# A540R260_ARM2.net
KiCad netlist of a schematic drawn in Altium Designer
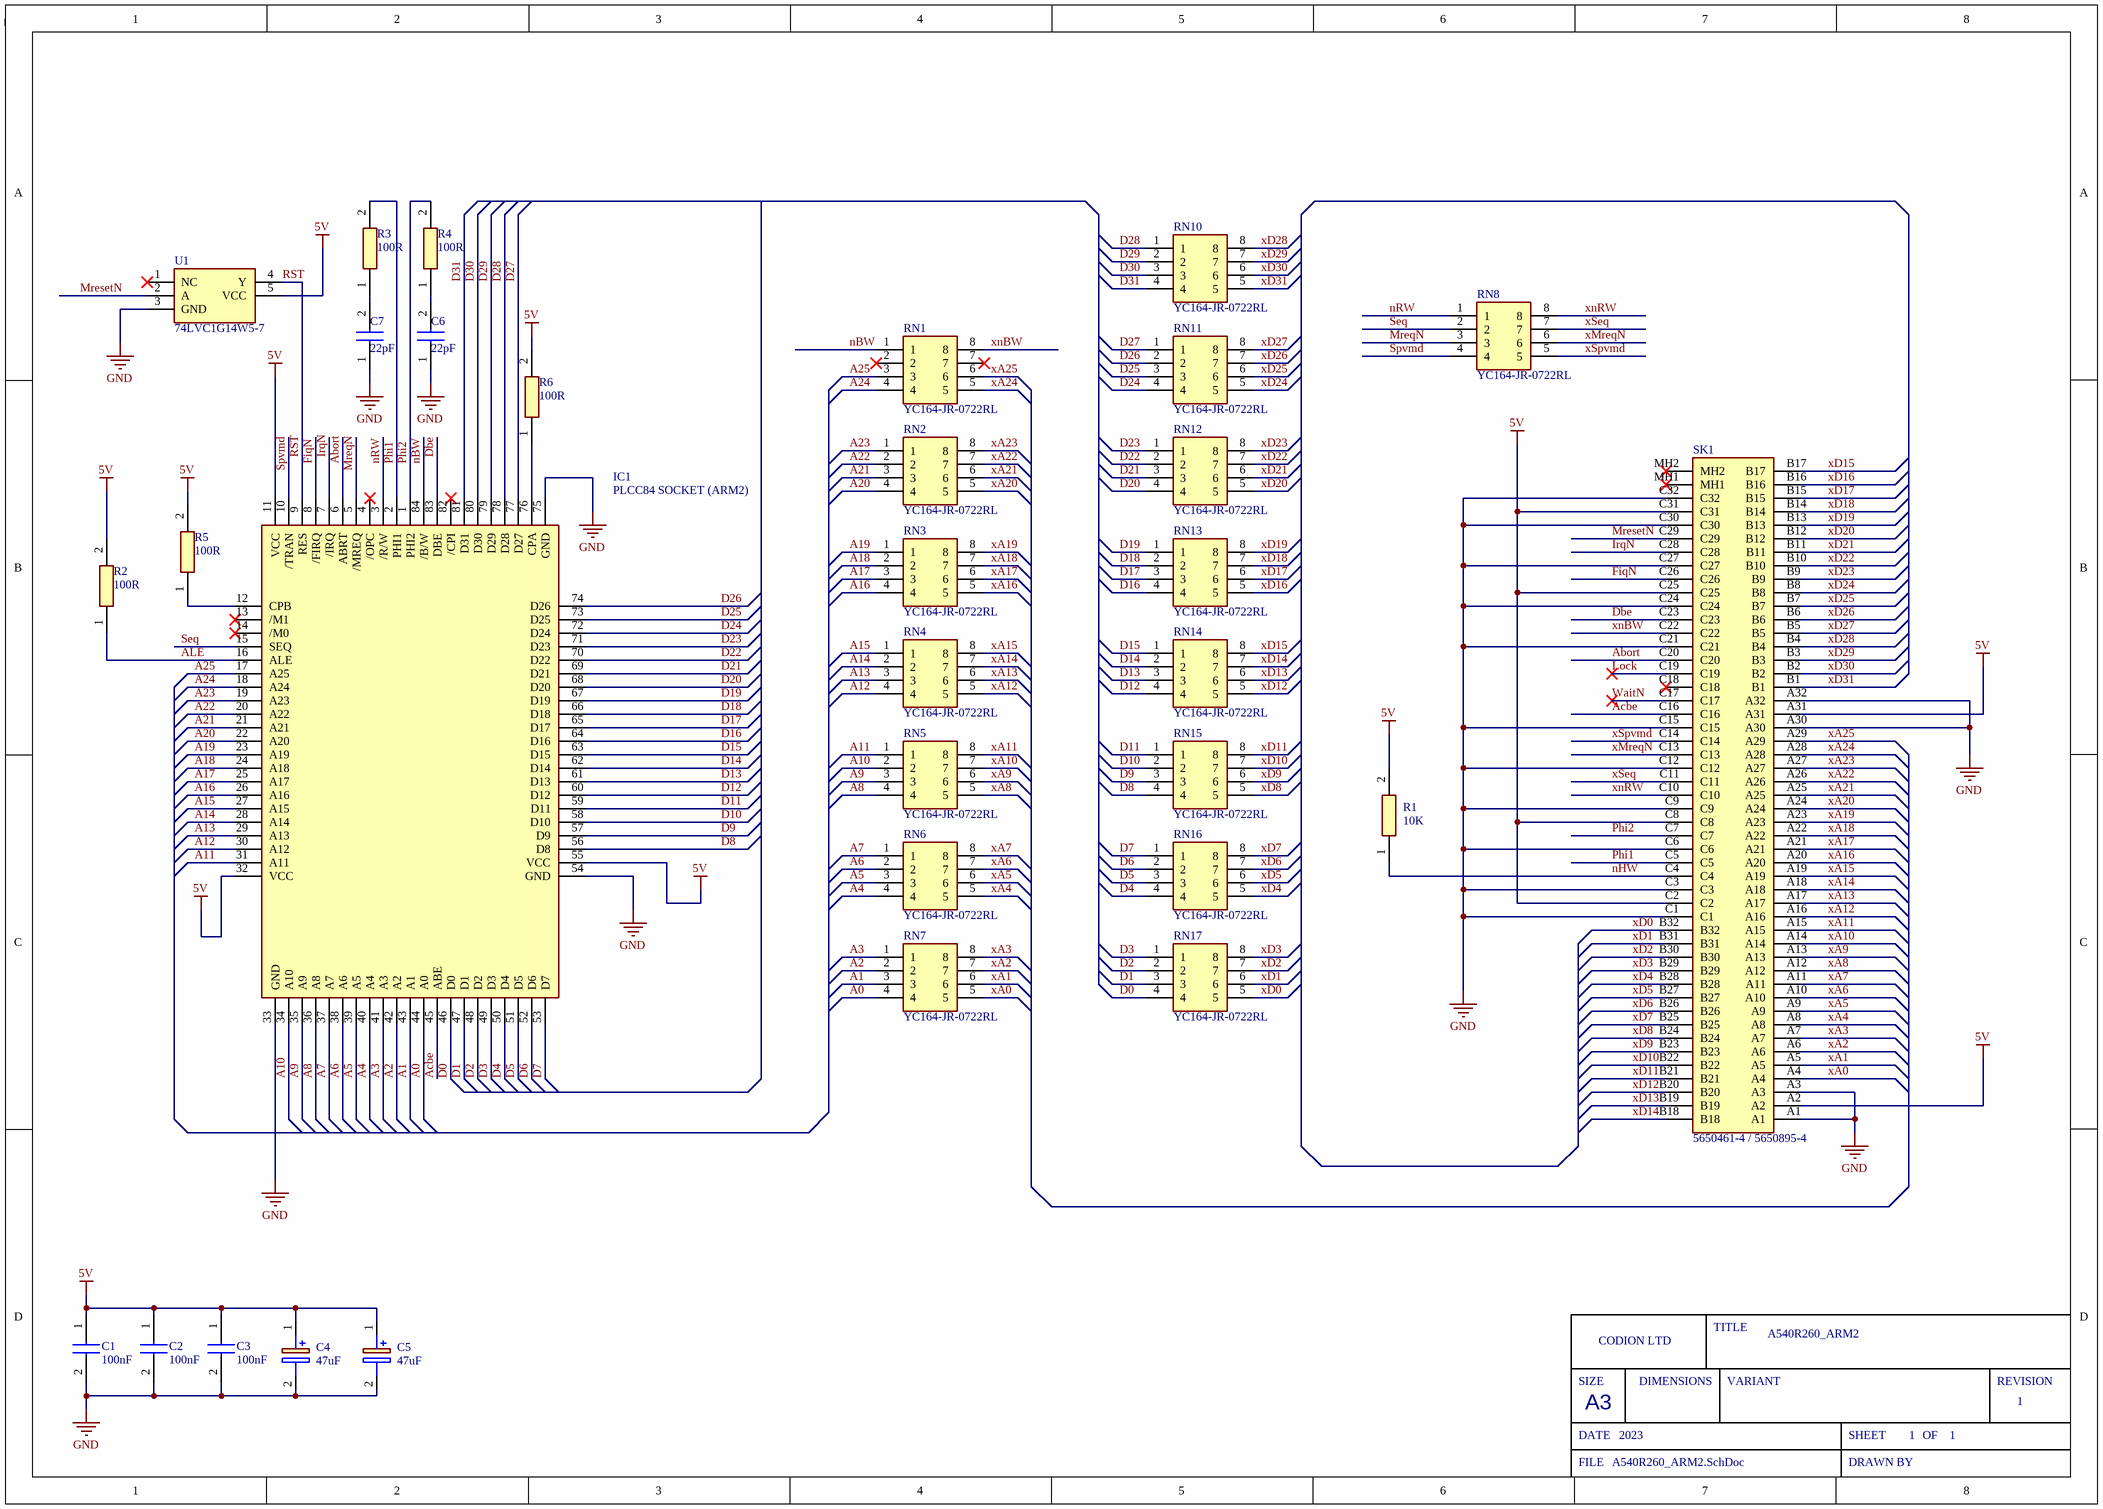
[diagram p0: A540R260_ARM2.SchDoc]

(export (version "E")
  (design (tool "Eeschema 10.0.6"))
  (components
    (comp (ref "C1")
      (value "100nF")
      (footprint "SamacSys:CAPC2012X145N")
      (description "Capacitor")
      (fields
        (field (name "MANUFACTURER_PART_NUMBER") "C2012X7R1H104K125AM")
        (field (name "MOUSER PART NUMBER") "810-C2012X7R1H104KT5")
      )
      (libsource (lib "*") (part "C2012X7R1H104K125AM"))
    )
    (comp (ref "C2")
      (value "100nF")
      (footprint "SamacSys:CAPC2012X145N")
      (description "Capacitor")
      (fields
        (field (name "MANUFACTURER_PART_NUMBER") "C2012X7R1H104K125AM")
        (field (name "MOUSER PART NUMBER") "810-C2012X7R1H104KT5")
      )
      (libsource (lib "*") (part "C2012X7R1H104K125AM"))
    )
    (comp (ref "C3")
      (value "100nF")
      (footprint "SamacSys:CAPC2012X145N")
      (description "Capacitor")
      (fields
        (field (name "MANUFACTURER_PART_NUMBER") "C2012X7R1H104K125AM")
        (field (name "MOUSER PART NUMBER") "810-C2012X7R1H104KT5")
      )
      (libsource (lib "*") (part "C2012X7R1H104K125AM"))
    )
    (comp (ref "C4")
      (value "47uF")
      (footprint "SamacSys:EEE1AA101SP")
      (description "Capacitor Polarised")
      (fields (field (name "MANUFACTURER_PART_NUMBER") "EEE1VA470WP"))
      (libsource (lib "*") (part "EEE1VA470WP"))
    )
    (comp (ref "C5")
      (value "47uF")
      (footprint "SamacSys:EEE1AA101SP")
      (description "Capacitor Polarised")
      (fields (field (name "MANUFACTURER_PART_NUMBER") "EEE1VA470WP"))
      (libsource (lib "*") (part "EEE1VA470WP"))
    )
    (comp (ref "C6")
      (value "22pF")
      (footprint "SamacSys:C0805")
      (description "Capacitor")
      (fields
        (field (name "MANUFACTURER_PART_NUMBER") "C0805C220J5GACTU")
        (field (name "MOUSER PART NUMBER") "80-C0805C220J5G")
      )
      (libsource (lib "*") (part "C0805C220J5GACTU"))
    )
    (comp (ref "C7")
      (value "22pF")
      (footprint "SamacSys:C0805")
      (description "Capacitor")
      (fields
        (field (name "MANUFACTURER_PART_NUMBER") "C0805C220J5GACTU")
        (field (name "MOUSER PART NUMBER") "80-C0805C220J5G")
      )
      (libsource (lib "*") (part "C0805C220J5GACTU"))
    )
    (comp (ref "IC1")
      (value "PLCC84 SOCKET (ARM2)")
      (footprint "PLCC84_PLUG")
      (description "PLCC84 Plug")
      (fields (field (name "MANUFACTURER_PART_NUMBER") "W9328"))
      (libsource (lib "ARM2toARM3Adapter") (part "PLCC84_PLUG_ARM2"))
    )
    (comp (ref "R1")
      (value "10K")
      (footprint "SamacSys:RESC2012X60N")
      (description "Resistor")
      (fields
        (field (name "MANUFACTURER_PART_NUMBER") "RC0805JR-0710KL")
        (field (name "MOUSER PART NUMBER") "603-RC0805JR-0710KL")
      )
      (libsource (lib "*") (part "RC0805JR-0710KL"))
    )
    (comp (ref "R2")
      (value "100R")
      (footprint "SamacSys:RESC2012X60N")
      (description "Resistor")
      (fields
        (field (name "MANUFACTURER_PART_NUMBER") "RC0805FR-07100RL")
        (field (name "MOUSER PART NUMBER") "603-RC0805FR-07100RL")
      )
      (libsource (lib "*") (part "RC0805FR-07100RL"))
    )
    (comp (ref "R3")
      (value "100R")
      (footprint "SamacSys:RESC2012X60N")
      (description "Resistor")
      (fields
        (field (name "MANUFACTURER_PART_NUMBER") "RC0805FR-07100RL")
        (field (name "MOUSER PART NUMBER") "603-RC0805FR-07100RL")
      )
      (libsource (lib "*") (part "RC0805FR-07100RL"))
    )
    (comp (ref "R4")
      (value "100R")
      (footprint "SamacSys:RESC2012X60N")
      (description "Resistor")
      (fields
        (field (name "MANUFACTURER_PART_NUMBER") "RC0805FR-07100RL")
        (field (name "MOUSER PART NUMBER") "603-RC0805FR-07100RL")
      )
      (libsource (lib "*") (part "RC0805FR-07100RL"))
    )
    (comp (ref "R5")
      (value "100R")
      (footprint "SamacSys:RESC2012X60N")
      (description "Resistor")
      (fields
        (field (name "MANUFACTURER_PART_NUMBER") "RC0805FR-07100RL")
        (field (name "MOUSER PART NUMBER") "603-RC0805FR-07100RL")
      )
      (libsource (lib "*") (part "RC0805FR-07100RL"))
    )
    (comp (ref "R6")
      (value "100R")
      (footprint "SamacSys:RESC2012X60N")
      (description "Resistor")
      (fields
        (field (name "MANUFACTURER_PART_NUMBER") "RC0805FR-07100RL")
        (field (name "MOUSER PART NUMBER") "603-RC0805FR-07100RL")
      )
      (libsource (lib "*") (part "RC0805FR-07100RL"))
    )
    (comp (ref "RN1")
      (value "YC164-JR-0722RL")
      (footprint "SamacSys:YC164JR072K2L")
      (description "Resistor Network")
      (fields (field (name "MOUSER PART NUMBER") "603-YC164-JR-0722RL"))
      (libsource (lib "*") (part "YC164-JR-0722RL"))
    )
    (comp (ref "RN2")
      (value "YC164-JR-0722RL")
      (footprint "SamacSys:YC164JR072K2L")
      (description "Resistor Network")
      (fields (field (name "MOUSER PART NUMBER") "603-YC164-JR-0722RL"))
      (libsource (lib "*") (part "YC164-JR-0722RL"))
    )
    (comp (ref "RN3")
      (value "YC164-JR-0722RL")
      (footprint "SamacSys:YC164JR072K2L")
      (description "Resistor Network")
      (fields (field (name "MOUSER PART NUMBER") "603-YC164-JR-0722RL"))
      (libsource (lib "*") (part "YC164-JR-0722RL"))
    )
    (comp (ref "RN4")
      (value "YC164-JR-0722RL")
      (footprint "SamacSys:YC164JR072K2L")
      (description "Resistor Network")
      (fields (field (name "MOUSER PART NUMBER") "603-YC164-JR-0722RL"))
      (libsource (lib "*") (part "YC164-JR-0722RL"))
    )
    (comp (ref "RN5")
      (value "YC164-JR-0722RL")
      (footprint "SamacSys:YC164JR072K2L")
      (description "Resistor Network")
      (fields (field (name "MOUSER PART NUMBER") "603-YC164-JR-0722RL"))
      (libsource (lib "*") (part "YC164-JR-0722RL"))
    )
    (comp (ref "RN6")
      (value "YC164-JR-0722RL")
      (footprint "SamacSys:YC164JR072K2L")
      (description "Resistor Network")
      (fields (field (name "MOUSER PART NUMBER") "603-YC164-JR-0722RL"))
      (libsource (lib "*") (part "YC164-JR-0722RL"))
    )
    (comp (ref "RN7")
      (value "YC164-JR-0722RL")
      (footprint "SamacSys:YC164JR072K2L")
      (description "Resistor Network")
      (fields (field (name "MOUSER PART NUMBER") "603-YC164-JR-0722RL"))
      (libsource (lib "*") (part "YC164-JR-0722RL"))
    )
    (comp (ref "RN8")
      (value "YC164-JR-0722RL")
      (footprint "SamacSys:YC164JR072K2L")
      (description "Resistor Network")
      (fields (field (name "MOUSER PART NUMBER") "603-YC164-JR-0722RL"))
      (libsource (lib "*") (part "YC164-JR-0722RL"))
    )
    (comp (ref "RN10")
      (value "YC164-JR-0722RL")
      (footprint "SamacSys:YC164JR072K2L")
      (description "Resistor Network")
      (fields (field (name "MOUSER PART NUMBER") "603-YC164-JR-0722RL"))
      (libsource (lib "*") (part "YC164-JR-0722RL"))
    )
    (comp (ref "RN11")
      (value "YC164-JR-0722RL")
      (footprint "SamacSys:YC164JR072K2L")
      (description "Resistor Network")
      (fields (field (name "MOUSER PART NUMBER") "603-YC164-JR-0722RL"))
      (libsource (lib "*") (part "YC164-JR-0722RL"))
    )
    (comp (ref "RN12")
      (value "YC164-JR-0722RL")
      (footprint "SamacSys:YC164JR072K2L")
      (description "Resistor Network")
      (fields (field (name "MOUSER PART NUMBER") "603-YC164-JR-0722RL"))
      (libsource (lib "*") (part "YC164-JR-0722RL"))
    )
    (comp (ref "RN13")
      (value "YC164-JR-0722RL")
      (footprint "SamacSys:YC164JR072K2L")
      (description "Resistor Network")
      (fields (field (name "MOUSER PART NUMBER") "603-YC164-JR-0722RL"))
      (libsource (lib "*") (part "YC164-JR-0722RL"))
    )
    (comp (ref "RN14")
      (value "YC164-JR-0722RL")
      (footprint "SamacSys:YC164JR072K2L")
      (description "Resistor Network")
      (fields (field (name "MOUSER PART NUMBER") "603-YC164-JR-0722RL"))
      (libsource (lib "*") (part "YC164-JR-0722RL"))
    )
    (comp (ref "RN15")
      (value "YC164-JR-0722RL")
      (footprint "SamacSys:YC164JR072K2L")
      (description "Resistor Network")
      (fields (field (name "MOUSER PART NUMBER") "603-YC164-JR-0722RL"))
      (libsource (lib "*") (part "YC164-JR-0722RL"))
    )
    (comp (ref "RN16")
      (value "YC164-JR-0722RL")
      (footprint "SamacSys:YC164JR072K2L")
      (description "Resistor Network")
      (fields (field (name "MOUSER PART NUMBER") "603-YC164-JR-0722RL"))
      (libsource (lib "*") (part "YC164-JR-0722RL"))
    )
    (comp (ref "RN17")
      (value "YC164-JR-0722RL")
      (footprint "SamacSys:YC164JR072K2L")
      (description "Resistor Network")
      (fields (field (name "MOUSER PART NUMBER") "603-YC164-JR-0722RL"))
      (libsource (lib "*") (part "YC164-JR-0722RL"))
    )
    (comp (ref "SK1")
      (value "5650461-4 / 5650895-4")
      (footprint "SamacSys:56504614")
      (description "Connector")
      (fields
        (field (name "MANUFACTURER_PART_NUMBER") "5650461-4")
        (field (name "MOUSER PART NUMBER") "571-5650461-4")
      )
      (libsource (lib "*") (part "5650461-4"))
    )
    (comp (ref "U1")
      (value "74LVC1G14W5-7")
      (footprint "SamacSys:SOT95P285X140-5N")
      (description "Undefined or Miscellaneous")
      (fields (field (name "MOUSER PART NUMBER") "621-74LVC1G14W5-7"))
      (libsource (lib "*") (part "74LVC1G14W5-7"))
    )
  )
  (nets
    (net (code "1") (name "/A0") (class "Default")
      (node (ref "IC1") (pin "44") (pinfunction "A0_44") (pintype "passive"))
      (node (ref "RN7") (pin "4") (pinfunction "4_4") (pintype "passive"))
    )
    (net (code "2") (name "/A1") (class "Default")
      (node (ref "IC1") (pin "43") (pinfunction "A1_43") (pintype "passive"))
      (node (ref "RN7") (pin "3") (pinfunction "3_3") (pintype "passive"))
    )
    (net (code "3") (name "/A2") (class "Default")
      (node (ref "IC1") (pin "42") (pinfunction "A2_42") (pintype "passive"))
      (node (ref "RN7") (pin "2") (pinfunction "2_2") (pintype "passive"))
    )
    (net (code "4") (name "/A3") (class "Default")
      (node (ref "IC1") (pin "41") (pinfunction "A3_41") (pintype "passive"))
      (node (ref "RN7") (pin "1") (pinfunction "1_1") (pintype "passive"))
    )
    (net (code "5") (name "/A4") (class "Default")
      (node (ref "IC1") (pin "40") (pinfunction "A4_40") (pintype "passive"))
      (node (ref "RN6") (pin "4") (pinfunction "4_4") (pintype "passive"))
    )
    (net (code "6") (name "/A5") (class "Default")
      (node (ref "IC1") (pin "39") (pinfunction "A5_39") (pintype "passive"))
      (node (ref "RN6") (pin "3") (pinfunction "3_3") (pintype "passive"))
    )
    (net (code "7") (name "/A6") (class "Default")
      (node (ref "IC1") (pin "38") (pinfunction "A6_38") (pintype "passive"))
      (node (ref "RN6") (pin "2") (pinfunction "2_2") (pintype "passive"))
    )
    (net (code "8") (name "/A7") (class "Default")
      (node (ref "IC1") (pin "37") (pinfunction "A7_37") (pintype "passive"))
      (node (ref "RN6") (pin "1") (pinfunction "1_1") (pintype "passive"))
    )
    (net (code "9") (name "/A8") (class "Default")
      (node (ref "IC1") (pin "36") (pinfunction "A8_36") (pintype "passive"))
      (node (ref "RN5") (pin "4") (pinfunction "4_4") (pintype "passive"))
    )
    (net (code "10") (name "/A9") (class "Default")
      (node (ref "IC1") (pin "35") (pinfunction "A9_35") (pintype "passive"))
      (node (ref "RN5") (pin "3") (pinfunction "3_3") (pintype "passive"))
    )
    (net (code "11") (name "/A10") (class "Default")
      (node (ref "IC1") (pin "34") (pinfunction "A10_34") (pintype "passive"))
      (node (ref "RN5") (pin "2") (pinfunction "2_2") (pintype "passive"))
    )
    (net (code "12") (name "/A11") (class "Default")
      (node (ref "IC1") (pin "31") (pinfunction "A11_31") (pintype "passive"))
      (node (ref "RN5") (pin "1") (pinfunction "1_1") (pintype "passive"))
    )
    (net (code "13") (name "/A12") (class "Default")
      (node (ref "IC1") (pin "30") (pinfunction "A12_30") (pintype "passive"))
      (node (ref "RN4") (pin "4") (pinfunction "4_4") (pintype "passive"))
    )
    (net (code "14") (name "/A13") (class "Default")
      (node (ref "IC1") (pin "29") (pinfunction "A13_29") (pintype "passive"))
      (node (ref "RN4") (pin "3") (pinfunction "3_3") (pintype "passive"))
    )
    (net (code "15") (name "/A14") (class "Default")
      (node (ref "IC1") (pin "28") (pinfunction "A14_28") (pintype "passive"))
      (node (ref "RN4") (pin "2") (pinfunction "2_2") (pintype "passive"))
    )
    (net (code "16") (name "/A15") (class "Default")
      (node (ref "IC1") (pin "27") (pinfunction "A15_27") (pintype "passive"))
      (node (ref "RN4") (pin "1") (pinfunction "1_1") (pintype "passive"))
    )
    (net (code "17") (name "/A16") (class "Default")
      (node (ref "IC1") (pin "26") (pinfunction "A16_26") (pintype "passive"))
      (node (ref "RN3") (pin "4") (pinfunction "4_4") (pintype "passive"))
    )
    (net (code "18") (name "/A17") (class "Default")
      (node (ref "IC1") (pin "25") (pinfunction "A17_25") (pintype "passive"))
      (node (ref "RN3") (pin "3") (pinfunction "3_3") (pintype "passive"))
    )
    (net (code "19") (name "/A18") (class "Default")
      (node (ref "IC1") (pin "24") (pinfunction "A18_24") (pintype "passive"))
      (node (ref "RN3") (pin "2") (pinfunction "2_2") (pintype "passive"))
    )
    (net (code "20") (name "/A19") (class "Default")
      (node (ref "IC1") (pin "23") (pinfunction "A19_23") (pintype "passive"))
      (node (ref "RN3") (pin "1") (pinfunction "1_1") (pintype "passive"))
    )
    (net (code "21") (name "/A20") (class "Default")
      (node (ref "IC1") (pin "22") (pinfunction "A20_22") (pintype "passive"))
      (node (ref "RN2") (pin "4") (pinfunction "4_4") (pintype "passive"))
    )
    (net (code "22") (name "/A21") (class "Default")
      (node (ref "IC1") (pin "21") (pinfunction "A21_21") (pintype "passive"))
      (node (ref "RN2") (pin "3") (pinfunction "3_3") (pintype "passive"))
    )
    (net (code "23") (name "/A22") (class "Default")
      (node (ref "IC1") (pin "20") (pinfunction "A22_20") (pintype "passive"))
      (node (ref "RN2") (pin "2") (pinfunction "2_2") (pintype "passive"))
    )
    (net (code "24") (name "/A23") (class "Default")
      (node (ref "IC1") (pin "19") (pinfunction "A23_19") (pintype "passive"))
      (node (ref "RN2") (pin "1") (pinfunction "1_1") (pintype "passive"))
    )
    (net (code "25") (name "/A24") (class "Default")
      (node (ref "IC1") (pin "18") (pinfunction "A24_18") (pintype "passive"))
      (node (ref "RN1") (pin "4") (pinfunction "4_4") (pintype "passive"))
    )
    (net (code "26") (name "/A25") (class "Default")
      (node (ref "IC1") (pin "17") (pinfunction "A25_17") (pintype "passive"))
      (node (ref "RN1") (pin "3") (pinfunction "3_3") (pintype "passive"))
    )
    (net (code "27") (name "/ALE") (class "Default")
      (node (ref "IC1") (pin "16") (pinfunction "ALE_16") (pintype "passive"))
      (node (ref "R2") (pin "1") (pinfunction "1_1") (pintype "passive"))
    )
    (net (code "28") (name "/Abort") (class "Default")
      (node (ref "IC1") (pin "6") (pinfunction "ABRT_6") (pintype "passive"))
      (node (ref "SK1") (pin "C20") (pinfunction "C20_C20") (pintype "passive"))
    )
    (net (code "29") (name "/Acbe") (class "Default")
      (node (ref "IC1") (pin "45") (pinfunction "ABE_45") (pintype "passive"))
      (node (ref "SK1") (pin "C16") (pinfunction "C16_C16") (pintype "passive"))
    )
    (net (code "30") (name "/D0") (class "Default")
      (node (ref "IC1") (pin "46") (pinfunction "D0_46") (pintype "passive"))
      (node (ref "RN17") (pin "4") (pinfunction "4_4") (pintype "passive"))
    )
    (net (code "31") (name "/D1") (class "Default")
      (node (ref "IC1") (pin "47") (pinfunction "D1_47") (pintype "passive"))
      (node (ref "RN17") (pin "3") (pinfunction "3_3") (pintype "passive"))
    )
    (net (code "32") (name "/D2") (class "Default")
      (node (ref "IC1") (pin "48") (pinfunction "D2_48") (pintype "passive"))
      (node (ref "RN17") (pin "2") (pinfunction "2_2") (pintype "passive"))
    )
    (net (code "33") (name "/D3") (class "Default")
      (node (ref "IC1") (pin "49") (pinfunction "D3_49") (pintype "passive"))
      (node (ref "RN17") (pin "1") (pinfunction "1_1") (pintype "passive"))
    )
    (net (code "34") (name "/D4") (class "Default")
      (node (ref "IC1") (pin "50") (pinfunction "D4_50") (pintype "passive"))
      (node (ref "RN16") (pin "4") (pinfunction "4_4") (pintype "passive"))
    )
    (net (code "35") (name "/D5") (class "Default")
      (node (ref "IC1") (pin "51") (pinfunction "D5_51") (pintype "passive"))
      (node (ref "RN16") (pin "3") (pinfunction "3_3") (pintype "passive"))
    )
    (net (code "36") (name "/D6") (class "Default")
      (node (ref "IC1") (pin "52") (pinfunction "D6_52") (pintype "passive"))
      (node (ref "RN16") (pin "2") (pinfunction "2_2") (pintype "passive"))
    )
    (net (code "37") (name "/D7") (class "Default")
      (node (ref "IC1") (pin "53") (pinfunction "D7_53") (pintype "passive"))
      (node (ref "RN16") (pin "1") (pinfunction "1_1") (pintype "passive"))
    )
    (net (code "38") (name "/D8") (class "Default")
      (node (ref "IC1") (pin "56") (pinfunction "D8_56") (pintype "passive"))
      (node (ref "RN15") (pin "4") (pinfunction "4_4") (pintype "passive"))
    )
    (net (code "39") (name "/D9") (class "Default")
      (node (ref "IC1") (pin "57") (pinfunction "D9_57") (pintype "passive"))
      (node (ref "RN15") (pin "3") (pinfunction "3_3") (pintype "passive"))
    )
    (net (code "40") (name "/D10") (class "Default")
      (node (ref "IC1") (pin "58") (pinfunction "D10_58") (pintype "passive"))
      (node (ref "RN15") (pin "2") (pinfunction "2_2") (pintype "passive"))
    )
    (net (code "41") (name "/D11") (class "Default")
      (node (ref "IC1") (pin "59") (pinfunction "D11_59") (pintype "passive"))
      (node (ref "RN15") (pin "1") (pinfunction "1_1") (pintype "passive"))
    )
    (net (code "42") (name "/D12") (class "Default")
      (node (ref "IC1") (pin "60") (pinfunction "D12_60") (pintype "passive"))
      (node (ref "RN14") (pin "4") (pinfunction "4_4") (pintype "passive"))
    )
    (net (code "43") (name "/D13") (class "Default")
      (node (ref "IC1") (pin "61") (pinfunction "D13_61") (pintype "passive"))
      (node (ref "RN14") (pin "3") (pinfunction "3_3") (pintype "passive"))
    )
    (net (code "44") (name "/D14") (class "Default")
      (node (ref "IC1") (pin "62") (pinfunction "D14_62") (pintype "passive"))
      (node (ref "RN14") (pin "2") (pinfunction "2_2") (pintype "passive"))
    )
    (net (code "45") (name "/D15") (class "Default")
      (node (ref "IC1") (pin "63") (pinfunction "D15_63") (pintype "passive"))
      (node (ref "RN14") (pin "1") (pinfunction "1_1") (pintype "passive"))
    )
    (net (code "46") (name "/D16") (class "Default")
      (node (ref "IC1") (pin "64") (pinfunction "D16_64") (pintype "passive"))
      (node (ref "RN13") (pin "4") (pinfunction "4_4") (pintype "passive"))
    )
    (net (code "47") (name "/D17") (class "Default")
      (node (ref "IC1") (pin "65") (pinfunction "D17_65") (pintype "passive"))
      (node (ref "RN13") (pin "3") (pinfunction "3_3") (pintype "passive"))
    )
    (net (code "48") (name "/D18") (class "Default")
      (node (ref "IC1") (pin "66") (pinfunction "D18_66") (pintype "passive"))
      (node (ref "RN13") (pin "2") (pinfunction "2_2") (pintype "passive"))
    )
    (net (code "49") (name "/D19") (class "Default")
      (node (ref "IC1") (pin "67") (pinfunction "D19_67") (pintype "passive"))
      (node (ref "RN13") (pin "1") (pinfunction "1_1") (pintype "passive"))
    )
    (net (code "50") (name "/D20") (class "Default")
      (node (ref "IC1") (pin "68") (pinfunction "D20_68") (pintype "passive"))
      (node (ref "RN12") (pin "4") (pinfunction "4_4") (pintype "passive"))
    )
    (net (code "51") (name "/D21") (class "Default")
      (node (ref "IC1") (pin "69") (pinfunction "D21_69") (pintype "passive"))
      (node (ref "RN12") (pin "3") (pinfunction "3_3") (pintype "passive"))
    )
    (net (code "52") (name "/D22") (class "Default")
      (node (ref "IC1") (pin "70") (pinfunction "D22_70") (pintype "passive"))
      (node (ref "RN12") (pin "2") (pinfunction "2_2") (pintype "passive"))
    )
    (net (code "53") (name "/D23") (class "Default")
      (node (ref "IC1") (pin "71") (pinfunction "D23_71") (pintype "passive"))
      (node (ref "RN12") (pin "1") (pinfunction "1_1") (pintype "passive"))
    )
    (net (code "54") (name "/D24") (class "Default")
      (node (ref "IC1") (pin "72") (pinfunction "D24_72") (pintype "passive"))
      (node (ref "RN11") (pin "4") (pinfunction "4_4") (pintype "passive"))
    )
    (net (code "55") (name "/D25") (class "Default")
      (node (ref "IC1") (pin "73") (pinfunction "D25_73") (pintype "passive"))
      (node (ref "RN11") (pin "3") (pinfunction "3_3") (pintype "passive"))
    )
    (net (code "56") (name "/D26") (class "Default")
      (node (ref "IC1") (pin "74") (pinfunction "D26_74") (pintype "passive"))
      (node (ref "RN11") (pin "2") (pinfunction "2_2") (pintype "passive"))
    )
    (net (code "57") (name "/D27") (class "Default")
      (node (ref "IC1") (pin "77") (pinfunction "D27_77") (pintype "passive"))
      (node (ref "RN11") (pin "1") (pinfunction "1_1") (pintype "passive"))
    )
    (net (code "58") (name "/D28") (class "Default")
      (node (ref "IC1") (pin "78") (pinfunction "D28_78") (pintype "passive"))
      (node (ref "RN10") (pin "1") (pinfunction "1_1") (pintype "passive"))
    )
    (net (code "59") (name "/D29") (class "Default")
      (node (ref "IC1") (pin "79") (pinfunction "D29_79") (pintype "passive"))
      (node (ref "RN10") (pin "2") (pinfunction "2_2") (pintype "passive"))
    )
    (net (code "60") (name "/D30") (class "Default")
      (node (ref "IC1") (pin "80") (pinfunction "D30_80") (pintype "passive"))
      (node (ref "RN10") (pin "3") (pinfunction "3_3") (pintype "passive"))
    )
    (net (code "61") (name "/D31") (class "Default")
      (node (ref "IC1") (pin "81") (pinfunction "D31_81") (pintype "passive"))
      (node (ref "RN10") (pin "4") (pinfunction "4_4") (pintype "passive"))
    )
    (net (code "62") (name "/Dbe") (class "Default")
      (node (ref "IC1") (pin "83") (pinfunction "DBE_83") (pintype "passive"))
      (node (ref "SK1") (pin "C23") (pinfunction "C23_C23") (pintype "passive"))
    )
    (net (code "63") (name "/FiqN") (class "Default")
      (node (ref "IC1") (pin "8") (pinfunction "/FIRQ_8") (pintype "passive"))
      (node (ref "SK1") (pin "C26") (pinfunction "C26_C26") (pintype "passive"))
    )
    (net (code "64") (name "/IrqN") (class "Default")
      (node (ref "IC1") (pin "7") (pinfunction "/IRQ_7") (pintype "passive"))
      (node (ref "SK1") (pin "C28") (pinfunction "C28_C28") (pintype "passive"))
    )
    (net (code "65") (name "/Lock") (class "Default")
      (node (ref "SK1") (pin "C19") (pinfunction "C19_C19") (pintype "passive+no_connect"))
    )
    (net (code "66") (name "/MreqN") (class "Default")
      (node (ref "IC1") (pin "5") (pinfunction "/MREQ_5") (pintype "passive"))
      (node (ref "RN8") (pin "3") (pinfunction "3_3") (pintype "passive"))
    )
    (net (code "67") (name "/MresetN") (class "Default")
      (node (ref "SK1") (pin "C29") (pinfunction "C29_C29") (pintype "passive"))
      (node (ref "U1") (pin "2") (pinfunction "A_2") (pintype "passive"))
    )
    (net (code "68") (name "/Phi1") (class "Default")
      (node (ref "IC1") (pin "2") (pinfunction "PHI1_2") (pintype "passive"))
      (node (ref "R3") (pin "2") (pinfunction "2_2") (pintype "passive"))
      (node (ref "SK1") (pin "C5") (pinfunction "C5_C5") (pintype "passive"))
    )
    (net (code "69") (name "/Phi2") (class "Default")
      (node (ref "IC1") (pin "1") (pinfunction "PHI2_1") (pintype "passive"))
      (node (ref "R4") (pin "2") (pinfunction "2_2") (pintype "passive"))
      (node (ref "SK1") (pin "C7") (pinfunction "C7_C7") (pintype "passive"))
    )
    (net (code "70") (name "/RST") (class "Default")
      (node (ref "IC1") (pin "9") (pinfunction "RES_9") (pintype "passive"))
      (node (ref "U1") (pin "4") (pinfunction "Y_4") (pintype "passive"))
    )
    (net (code "71") (name "/Seq") (class "Default")
      (node (ref "IC1") (pin "15") (pinfunction "SEQ_15") (pintype "passive"))
      (node (ref "RN8") (pin "2") (pinfunction "2_2") (pintype "passive"))
    )
    (net (code "72") (name "/Spvmd") (class "Default")
      (node (ref "IC1") (pin "10") (pinfunction "/TRAN_10") (pintype "passive"))
      (node (ref "RN8") (pin "4") (pinfunction "4_4") (pintype "passive"))
    )
    (net (code "73") (name "/WaitN") (class "Default")
      (node (ref "SK1") (pin "C17") (pinfunction "C17_C17") (pintype "passive+no_connect"))
    )
    (net (code "74") (name "/nBW") (class "Default")
      (node (ref "IC1") (pin "84") (pinfunction "/B/W_84") (pintype "passive"))
      (node (ref "RN1") (pin "1") (pinfunction "1_1") (pintype "passive"))
    )
    (net (code "75") (name "/nHW") (class "Default")
      (node (ref "R1") (pin "1") (pinfunction "1_1") (pintype "passive"))
      (node (ref "SK1") (pin "C4") (pinfunction "C4_C4") (pintype "passive"))
    )
    (net (code "76") (name "/nRW") (class "Default")
      (node (ref "IC1") (pin "3") (pinfunction "/R/W_3") (pintype "passive"))
      (node (ref "RN8") (pin "1") (pinfunction "1_1") (pintype "passive"))
    )
    (net (code "77") (name "/xA0") (class "Default")
      (node (ref "RN7") (pin "5") (pinfunction "5_5") (pintype "passive"))
      (node (ref "SK1") (pin "A4") (pinfunction "A4_A4") (pintype "passive"))
    )
    (net (code "78") (name "/xA1") (class "Default")
      (node (ref "RN7") (pin "6") (pinfunction "6_6") (pintype "passive"))
      (node (ref "SK1") (pin "A5") (pinfunction "A5_A5") (pintype "passive"))
    )
    (net (code "79") (name "/xA2") (class "Default")
      (node (ref "RN7") (pin "7") (pinfunction "7_7") (pintype "passive"))
      (node (ref "SK1") (pin "A6") (pinfunction "A6_A6") (pintype "passive"))
    )
    (net (code "80") (name "/xA3") (class "Default")
      (node (ref "RN7") (pin "8") (pinfunction "8_8") (pintype "passive"))
      (node (ref "SK1") (pin "A7") (pinfunction "A7_A7") (pintype "passive"))
    )
    (net (code "81") (name "/xA4") (class "Default")
      (node (ref "RN6") (pin "5") (pinfunction "5_5") (pintype "passive"))
      (node (ref "SK1") (pin "A8") (pinfunction "A8_A8") (pintype "passive"))
    )
    (net (code "82") (name "/xA5") (class "Default")
      (node (ref "RN6") (pin "6") (pinfunction "6_6") (pintype "passive"))
      (node (ref "SK1") (pin "A9") (pinfunction "A9_A9") (pintype "passive"))
    )
    (net (code "83") (name "/xA6") (class "Default")
      (node (ref "RN6") (pin "7") (pinfunction "7_7") (pintype "passive"))
      (node (ref "SK1") (pin "A10") (pinfunction "A10_A10") (pintype "passive"))
    )
    (net (code "84") (name "/xA7") (class "Default")
      (node (ref "RN6") (pin "8") (pinfunction "8_8") (pintype "passive"))
      (node (ref "SK1") (pin "A11") (pinfunction "A11_A11") (pintype "passive"))
    )
    (net (code "85") (name "/xA8") (class "Default")
      (node (ref "RN5") (pin "5") (pinfunction "5_5") (pintype "passive"))
      (node (ref "SK1") (pin "A12") (pinfunction "A12_A12") (pintype "passive"))
    )
    (net (code "86") (name "/xA9") (class "Default")
      (node (ref "RN5") (pin "6") (pinfunction "6_6") (pintype "passive"))
      (node (ref "SK1") (pin "A13") (pinfunction "A13_A13") (pintype "passive"))
    )
    (net (code "87") (name "/xA10") (class "Default")
      (node (ref "RN5") (pin "7") (pinfunction "7_7") (pintype "passive"))
      (node (ref "SK1") (pin "A14") (pinfunction "A14_A14") (pintype "passive"))
    )
    (net (code "88") (name "/xA11") (class "Default")
      (node (ref "RN5") (pin "8") (pinfunction "8_8") (pintype "passive"))
      (node (ref "SK1") (pin "A15") (pinfunction "A15_A15") (pintype "passive"))
    )
    (net (code "89") (name "/xA12") (class "Default")
      (node (ref "RN4") (pin "5") (pinfunction "5_5") (pintype "passive"))
      (node (ref "SK1") (pin "A16") (pinfunction "A16_A16") (pintype "passive"))
    )
    (net (code "90") (name "/xA13") (class "Default")
      (node (ref "RN4") (pin "6") (pinfunction "6_6") (pintype "passive"))
      (node (ref "SK1") (pin "A17") (pinfunction "A17_A17") (pintype "passive"))
    )
    (net (code "91") (name "/xA14") (class "Default")
      (node (ref "RN4") (pin "7") (pinfunction "7_7") (pintype "passive"))
      (node (ref "SK1") (pin "A18") (pinfunction "A18_A18") (pintype "passive"))
    )
    (net (code "92") (name "/xA15") (class "Default")
      (node (ref "RN4") (pin "8") (pinfunction "8_8") (pintype "passive"))
      (node (ref "SK1") (pin "A19") (pinfunction "A19_A19") (pintype "passive"))
    )
    (net (code "93") (name "/xA16") (class "Default")
      (node (ref "RN3") (pin "5") (pinfunction "5_5") (pintype "passive"))
      (node (ref "SK1") (pin "A20") (pinfunction "A20_A20") (pintype "passive"))
    )
    (net (code "94") (name "/xA17") (class "Default")
      (node (ref "RN3") (pin "6") (pinfunction "6_6") (pintype "passive"))
      (node (ref "SK1") (pin "A21") (pinfunction "A21_A21") (pintype "passive"))
    )
    (net (code "95") (name "/xA18") (class "Default")
      (node (ref "RN3") (pin "7") (pinfunction "7_7") (pintype "passive"))
      (node (ref "SK1") (pin "A22") (pinfunction "A22_A22") (pintype "passive"))
    )
    (net (code "96") (name "/xA19") (class "Default")
      (node (ref "RN3") (pin "8") (pinfunction "8_8") (pintype "passive"))
      (node (ref "SK1") (pin "A23") (pinfunction "A23_A23") (pintype "passive"))
    )
    (net (code "97") (name "/xA20") (class "Default")
      (node (ref "RN2") (pin "5") (pinfunction "5_5") (pintype "passive"))
      (node (ref "SK1") (pin "A24") (pinfunction "A24_A24") (pintype "passive"))
    )
    (net (code "98") (name "/xA21") (class "Default")
      (node (ref "RN2") (pin "6") (pinfunction "6_6") (pintype "passive"))
      (node (ref "SK1") (pin "A25") (pinfunction "A25_A25") (pintype "passive"))
    )
    (net (code "99") (name "/xA22") (class "Default")
      (node (ref "RN2") (pin "7") (pinfunction "7_7") (pintype "passive"))
      (node (ref "SK1") (pin "A26") (pinfunction "A26_A26") (pintype "passive"))
    )
    (net (code "100") (name "/xA23") (class "Default")
      (node (ref "RN2") (pin "8") (pinfunction "8_8") (pintype "passive"))
      (node (ref "SK1") (pin "A27") (pinfunction "A27_A27") (pintype "passive"))
    )
    (net (code "101") (name "/xA24") (class "Default")
      (node (ref "RN1") (pin "5") (pinfunction "5_5") (pintype "passive"))
      (node (ref "SK1") (pin "A28") (pinfunction "A28_A28") (pintype "passive"))
    )
    (net (code "102") (name "/xA25") (class "Default")
      (node (ref "RN1") (pin "6") (pinfunction "6_6") (pintype "passive"))
      (node (ref "SK1") (pin "A29") (pinfunction "A29_A29") (pintype "passive"))
    )
    (net (code "103") (name "/xD0") (class "Default")
      (node (ref "RN17") (pin "5") (pinfunction "5_5") (pintype "passive"))
      (node (ref "SK1") (pin "B32") (pinfunction "B32_B32") (pintype "passive"))
    )
    (net (code "104") (name "/xD1") (class "Default")
      (node (ref "RN17") (pin "6") (pinfunction "6_6") (pintype "passive"))
      (node (ref "SK1") (pin "B31") (pinfunction "B31_B31") (pintype "passive"))
    )
    (net (code "105") (name "/xD2") (class "Default")
      (node (ref "RN17") (pin "7") (pinfunction "7_7") (pintype "passive"))
      (node (ref "SK1") (pin "B30") (pinfunction "B30_B30") (pintype "passive"))
    )
    (net (code "106") (name "/xD3") (class "Default")
      (node (ref "RN17") (pin "8") (pinfunction "8_8") (pintype "passive"))
      (node (ref "SK1") (pin "B29") (pinfunction "B29_B29") (pintype "passive"))
    )
    (net (code "107") (name "/xD4") (class "Default")
      (node (ref "RN16") (pin "5") (pinfunction "5_5") (pintype "passive"))
      (node (ref "SK1") (pin "B28") (pinfunction "B28_B28") (pintype "passive"))
    )
    (net (code "108") (name "/xD5") (class "Default")
      (node (ref "RN16") (pin "6") (pinfunction "6_6") (pintype "passive"))
      (node (ref "SK1") (pin "B27") (pinfunction "B27_B27") (pintype "passive"))
    )
    (net (code "109") (name "/xD6") (class "Default")
      (node (ref "RN16") (pin "7") (pinfunction "7_7") (pintype "passive"))
      (node (ref "SK1") (pin "B26") (pinfunction "B26_B26") (pintype "passive"))
    )
    (net (code "110") (name "/xD7") (class "Default")
      (node (ref "RN16") (pin "8") (pinfunction "8_8") (pintype "passive"))
      (node (ref "SK1") (pin "B25") (pinfunction "B25_B25") (pintype "passive"))
    )
    (net (code "111") (name "/xD8") (class "Default")
      (node (ref "RN15") (pin "5") (pinfunction "5_5") (pintype "passive"))
      (node (ref "SK1") (pin "B24") (pinfunction "B24_B24") (pintype "passive"))
    )
    (net (code "112") (name "/xD9") (class "Default")
      (node (ref "RN15") (pin "6") (pinfunction "6_6") (pintype "passive"))
      (node (ref "SK1") (pin "B23") (pinfunction "B23_B23") (pintype "passive"))
    )
    (net (code "113") (name "/xD10") (class "Default")
      (node (ref "RN15") (pin "7") (pinfunction "7_7") (pintype "passive"))
      (node (ref "SK1") (pin "B22") (pinfunction "B22_B22") (pintype "passive"))
    )
    (net (code "114") (name "/xD11") (class "Default")
      (node (ref "RN15") (pin "8") (pinfunction "8_8") (pintype "passive"))
      (node (ref "SK1") (pin "B21") (pinfunction "B21_B21") (pintype "passive"))
    )
    (net (code "115") (name "/xD12") (class "Default")
      (node (ref "RN14") (pin "5") (pinfunction "5_5") (pintype "passive"))
      (node (ref "SK1") (pin "B20") (pinfunction "B20_B20") (pintype "passive"))
    )
    (net (code "116") (name "/xD13") (class "Default")
      (node (ref "RN14") (pin "6") (pinfunction "6_6") (pintype "passive"))
      (node (ref "SK1") (pin "B19") (pinfunction "B19_B19") (pintype "passive"))
    )
    (net (code "117") (name "/xD14") (class "Default")
      (node (ref "RN14") (pin "7") (pinfunction "7_7") (pintype "passive"))
      (node (ref "SK1") (pin "B18") (pinfunction "B18_B18") (pintype "passive"))
    )
    (net (code "118") (name "/xD15") (class "Default")
      (node (ref "RN14") (pin "8") (pinfunction "8_8") (pintype "passive"))
      (node (ref "SK1") (pin "B17") (pinfunction "B17_B17") (pintype "passive"))
    )
    (net (code "119") (name "/xD16") (class "Default")
      (node (ref "RN13") (pin "5") (pinfunction "5_5") (pintype "passive"))
      (node (ref "SK1") (pin "B16") (pinfunction "B16_B16") (pintype "passive"))
    )
    (net (code "120") (name "/xD17") (class "Default")
      (node (ref "RN13") (pin "6") (pinfunction "6_6") (pintype "passive"))
      (node (ref "SK1") (pin "B15") (pinfunction "B15_B15") (pintype "passive"))
    )
    (net (code "121") (name "/xD18") (class "Default")
      (node (ref "RN13") (pin "7") (pinfunction "7_7") (pintype "passive"))
      (node (ref "SK1") (pin "B14") (pinfunction "B14_B14") (pintype "passive"))
    )
    (net (code "122") (name "/xD19") (class "Default")
      (node (ref "RN13") (pin "8") (pinfunction "8_8") (pintype "passive"))
      (node (ref "SK1") (pin "B13") (pinfunction "B13_B13") (pintype "passive"))
    )
    (net (code "123") (name "/xD20") (class "Default")
      (node (ref "RN12") (pin "5") (pinfunction "5_5") (pintype "passive"))
      (node (ref "SK1") (pin "B12") (pinfunction "B12_B12") (pintype "passive"))
    )
    (net (code "124") (name "/xD21") (class "Default")
      (node (ref "RN12") (pin "6") (pinfunction "6_6") (pintype "passive"))
      (node (ref "SK1") (pin "B11") (pinfunction "B11_B11") (pintype "passive"))
    )
    (net (code "125") (name "/xD22") (class "Default")
      (node (ref "RN12") (pin "7") (pinfunction "7_7") (pintype "passive"))
      (node (ref "SK1") (pin "B10") (pinfunction "B10_B10") (pintype "passive"))
    )
    (net (code "126") (name "/xD23") (class "Default")
      (node (ref "RN12") (pin "8") (pinfunction "8_8") (pintype "passive"))
      (node (ref "SK1") (pin "B9") (pinfunction "B9_B9") (pintype "passive"))
    )
    (net (code "127") (name "/xD24") (class "Default")
      (node (ref "RN11") (pin "5") (pinfunction "5_5") (pintype "passive"))
      (node (ref "SK1") (pin "B8") (pinfunction "B8_B8") (pintype "passive"))
    )
    (net (code "128") (name "/xD25") (class "Default")
      (node (ref "RN11") (pin "6") (pinfunction "6_6") (pintype "passive"))
      (node (ref "SK1") (pin "B7") (pinfunction "B7_B7") (pintype "passive"))
    )
    (net (code "129") (name "/xD26") (class "Default")
      (node (ref "RN11") (pin "7") (pinfunction "7_7") (pintype "passive"))
      (node (ref "SK1") (pin "B6") (pinfunction "B6_B6") (pintype "passive"))
    )
    (net (code "130") (name "/xD27") (class "Default")
      (node (ref "RN11") (pin "8") (pinfunction "8_8") (pintype "passive"))
      (node (ref "SK1") (pin "B5") (pinfunction "B5_B5") (pintype "passive"))
    )
    (net (code "131") (name "/xD28") (class "Default")
      (node (ref "RN10") (pin "8") (pinfunction "8_8") (pintype "passive"))
      (node (ref "SK1") (pin "B4") (pinfunction "B4_B4") (pintype "passive"))
    )
    (net (code "132") (name "/xD29") (class "Default")
      (node (ref "RN10") (pin "7") (pinfunction "7_7") (pintype "passive"))
      (node (ref "SK1") (pin "B3") (pinfunction "B3_B3") (pintype "passive"))
    )
    (net (code "133") (name "/xD30") (class "Default")
      (node (ref "RN10") (pin "6") (pinfunction "6_6") (pintype "passive"))
      (node (ref "SK1") (pin "B2") (pinfunction "B2_B2") (pintype "passive"))
    )
    (net (code "134") (name "/xD31") (class "Default")
      (node (ref "RN10") (pin "5") (pinfunction "5_5") (pintype "passive"))
      (node (ref "SK1") (pin "B1") (pinfunction "B1_B1") (pintype "passive"))
    )
    (net (code "135") (name "/xMreqN") (class "Default")
      (node (ref "RN8") (pin "6") (pinfunction "6_6") (pintype "passive"))
      (node (ref "SK1") (pin "C13") (pinfunction "C13_C13") (pintype "passive"))
    )
    (net (code "136") (name "/xSeq") (class "Default")
      (node (ref "RN8") (pin "7") (pinfunction "7_7") (pintype "passive"))
      (node (ref "SK1") (pin "C11") (pinfunction "C11_C11") (pintype "passive"))
    )
    (net (code "137") (name "/xSpvmd") (class "Default")
      (node (ref "RN8") (pin "5") (pinfunction "5_5") (pintype "passive"))
      (node (ref "SK1") (pin "C14") (pinfunction "C14_C14") (pintype "passive"))
    )
    (net (code "138") (name "/xnBW") (class "Default")
      (node (ref "RN1") (pin "8") (pinfunction "8_8") (pintype "passive"))
      (node (ref "SK1") (pin "C22") (pinfunction "C22_C22") (pintype "passive"))
    )
    (net (code "139") (name "/xnRW") (class "Default")
      (node (ref "RN8") (pin "8") (pinfunction "8_8") (pintype "passive"))
      (node (ref "SK1") (pin "C10") (pinfunction "C10_C10") (pintype "passive"))
    )
    (net (code "140") (name "5V") (class "Default")
      (node (ref "C1") (pin "1") (pinfunction "1_1") (pintype "passive"))
      (node (ref "C2") (pin "1") (pinfunction "1_1") (pintype "passive"))
      (node (ref "C3") (pin "1") (pinfunction "1_1") (pintype "passive"))
      (node (ref "C4") (pin "1") (pinfunction "+_1") (pintype "passive"))
      (node (ref "C5") (pin "1") (pinfunction "+_1") (pintype "passive"))
      (node (ref "IC1") (pin "11") (pinfunction "VCC_11") (pintype "passive"))
      (node (ref "IC1") (pin "32") (pinfunction "VCC_32") (pintype "passive"))
      (node (ref "IC1") (pin "55") (pinfunction "VCC_55") (pintype "passive"))
      (node (ref "R1") (pin "2") (pinfunction "2_2") (pintype "passive"))
      (node (ref "R2") (pin "2") (pinfunction "2_2") (pintype "passive"))
      (node (ref "R5") (pin "2") (pinfunction "2_2") (pintype "passive"))
      (node (ref "R6") (pin "2") (pinfunction "2_2") (pintype "passive"))
      (node (ref "SK1") (pin "A2") (pinfunction "A2_A2") (pintype "passive"))
      (node (ref "SK1") (pin "A31") (pinfunction "A31_A31") (pintype "passive"))
      (node (ref "SK1") (pin "C2") (pinfunction "C2_C2") (pintype "passive"))
      (node (ref "SK1") (pin "C25") (pinfunction "C25_C25") (pintype "passive"))
      (node (ref "SK1") (pin "C31") (pinfunction "C31_C31") (pintype "passive"))
      (node (ref "SK1") (pin "C8") (pinfunction "C8_C8") (pintype "passive"))
      (node (ref "U1") (pin "5") (pinfunction "VCC_5") (pintype "passive"))
    )
    (net (code "141") (name "GND") (class "Default")
      (node (ref "C1") (pin "2") (pinfunction "2_2") (pintype "passive"))
      (node (ref "C2") (pin "2") (pinfunction "2_2") (pintype "passive"))
      (node (ref "C3") (pin "2") (pinfunction "2_2") (pintype "passive"))
      (node (ref "C4") (pin "2") (pinfunction "-_2") (pintype "passive"))
      (node (ref "C5") (pin "2") (pinfunction "-_2") (pintype "passive"))
      (node (ref "C6") (pin "1") (pinfunction "1_1") (pintype "passive"))
      (node (ref "C7") (pin "1") (pinfunction "1_1") (pintype "passive"))
      (node (ref "IC1") (pin "33") (pinfunction "GND_33") (pintype "passive"))
      (node (ref "IC1") (pin "54") (pinfunction "GND_54") (pintype "passive"))
      (node (ref "IC1") (pin "75") (pinfunction "GND_75") (pintype "passive"))
      (node (ref "SK1") (pin "A1") (pinfunction "A1_A1") (pintype "passive"))
      (node (ref "SK1") (pin "A3") (pinfunction "A3_A3") (pintype "passive"))
      (node (ref "SK1") (pin "A30") (pinfunction "A30_A30") (pintype "passive"))
      (node (ref "SK1") (pin "A32") (pinfunction "A32_A32") (pintype "passive"))
      (node (ref "SK1") (pin "C1") (pinfunction "C1_C1") (pintype "passive"))
      (node (ref "SK1") (pin "C12") (pinfunction "C12_C12") (pintype "passive"))
      (node (ref "SK1") (pin "C15") (pinfunction "C15_C15") (pintype "passive"))
      (node (ref "SK1") (pin "C21") (pinfunction "C21_C21") (pintype "passive"))
      (node (ref "SK1") (pin "C24") (pinfunction "C24_C24") (pintype "passive"))
      (node (ref "SK1") (pin "C27") (pinfunction "C27_C27") (pintype "passive"))
      (node (ref "SK1") (pin "C3") (pinfunction "C3_C3") (pintype "passive"))
      (node (ref "SK1") (pin "C30") (pinfunction "C30_C30") (pintype "passive"))
      (node (ref "SK1") (pin "C32") (pinfunction "C32_C32") (pintype "passive"))
      (node (ref "SK1") (pin "C6") (pinfunction "C6_C6") (pintype "passive"))
      (node (ref "SK1") (pin "C9") (pinfunction "C9_C9") (pintype "passive"))
      (node (ref "U1") (pin "3") (pinfunction "GND_3") (pintype "passive"))
    )
    (net (code "142") (name "Net-(C6-Pad2)") (class "Default")
      (node (ref "C6") (pin "2") (pinfunction "2_2") (pintype "passive"))
      (node (ref "R4") (pin "1") (pinfunction "1_1") (pintype "passive"))
    )
    (net (code "143") (name "Net-(C7-Pad2)") (class "Default")
      (node (ref "C7") (pin "2") (pinfunction "2_2") (pintype "passive"))
      (node (ref "R3") (pin "1") (pinfunction "1_1") (pintype "passive"))
    )
    (net (code "144") (name "Net-(IC1-CPA)") (class "Default")
      (node (ref "IC1") (pin "76") (pinfunction "CPA_76") (pintype "passive"))
      (node (ref "R6") (pin "1") (pinfunction "1_1") (pintype "passive"))
    )
    (net (code "145") (name "Net-(IC1-CPB)") (class "Default")
      (node (ref "IC1") (pin "12") (pinfunction "CPB_12") (pintype "passive"))
      (node (ref "R5") (pin "1") (pinfunction "1_1") (pintype "passive"))
    )
    (net (code "146") (name "unconnected-(IC1-{slash}CPI-Pad82)") (class "Default")
      (node (ref "IC1") (pin "82") (pinfunction "/CPI_82") (pintype "passive+no_connect"))
    )
    (net (code "147") (name "unconnected-(IC1-{slash}M0-Pad14)") (class "Default")
      (node (ref "IC1") (pin "14") (pinfunction "/M0_14") (pintype "passive+no_connect"))
    )
    (net (code "148") (name "unconnected-(IC1-{slash}M1-Pad13)") (class "Default")
      (node (ref "IC1") (pin "13") (pinfunction "/M1_13") (pintype "passive+no_connect"))
    )
    (net (code "149") (name "unconnected-(IC1-{slash}OPC-Pad4)") (class "Default")
      (node (ref "IC1") (pin "4") (pinfunction "/OPC_4") (pintype "passive+no_connect"))
    )
    (net (code "150") (name "unconnected-(RN1-Pad2)") (class "Default")
      (node (ref "RN1") (pin "2") (pinfunction "2_2") (pintype "passive+no_connect"))
    )
    (net (code "151") (name "unconnected-(RN1-Pad7)") (class "Default")
      (node (ref "RN1") (pin "7") (pinfunction "7_7") (pintype "passive+no_connect"))
    )
    (net (code "152") (name "unconnected-(SK1-PadC18)") (class "Default")
      (node (ref "SK1") (pin "C18") (pinfunction "C18_C18") (pintype "passive+no_connect"))
    )
    (net (code "153") (name "unconnected-(SK1-PadMH1)") (class "Default")
      (node (ref "SK1") (pin "MH1") (pinfunction "MH1_MH1") (pintype "passive+no_connect"))
    )
    (net (code "154") (name "unconnected-(SK1-PadMH2)") (class "Default")
      (node (ref "SK1") (pin "MH2") (pinfunction "MH2_MH2") (pintype "passive+no_connect"))
    )
    (net (code "155") (name "unconnected-(U1-NC-Pad1)") (class "Default")
      (node (ref "U1") (pin "1") (pinfunction "NC_1") (pintype "passive+no_connect"))
    )
  )
)
